# Micro_y_BT.net
KiCad netlist of a schematic drawn in Altium Designer
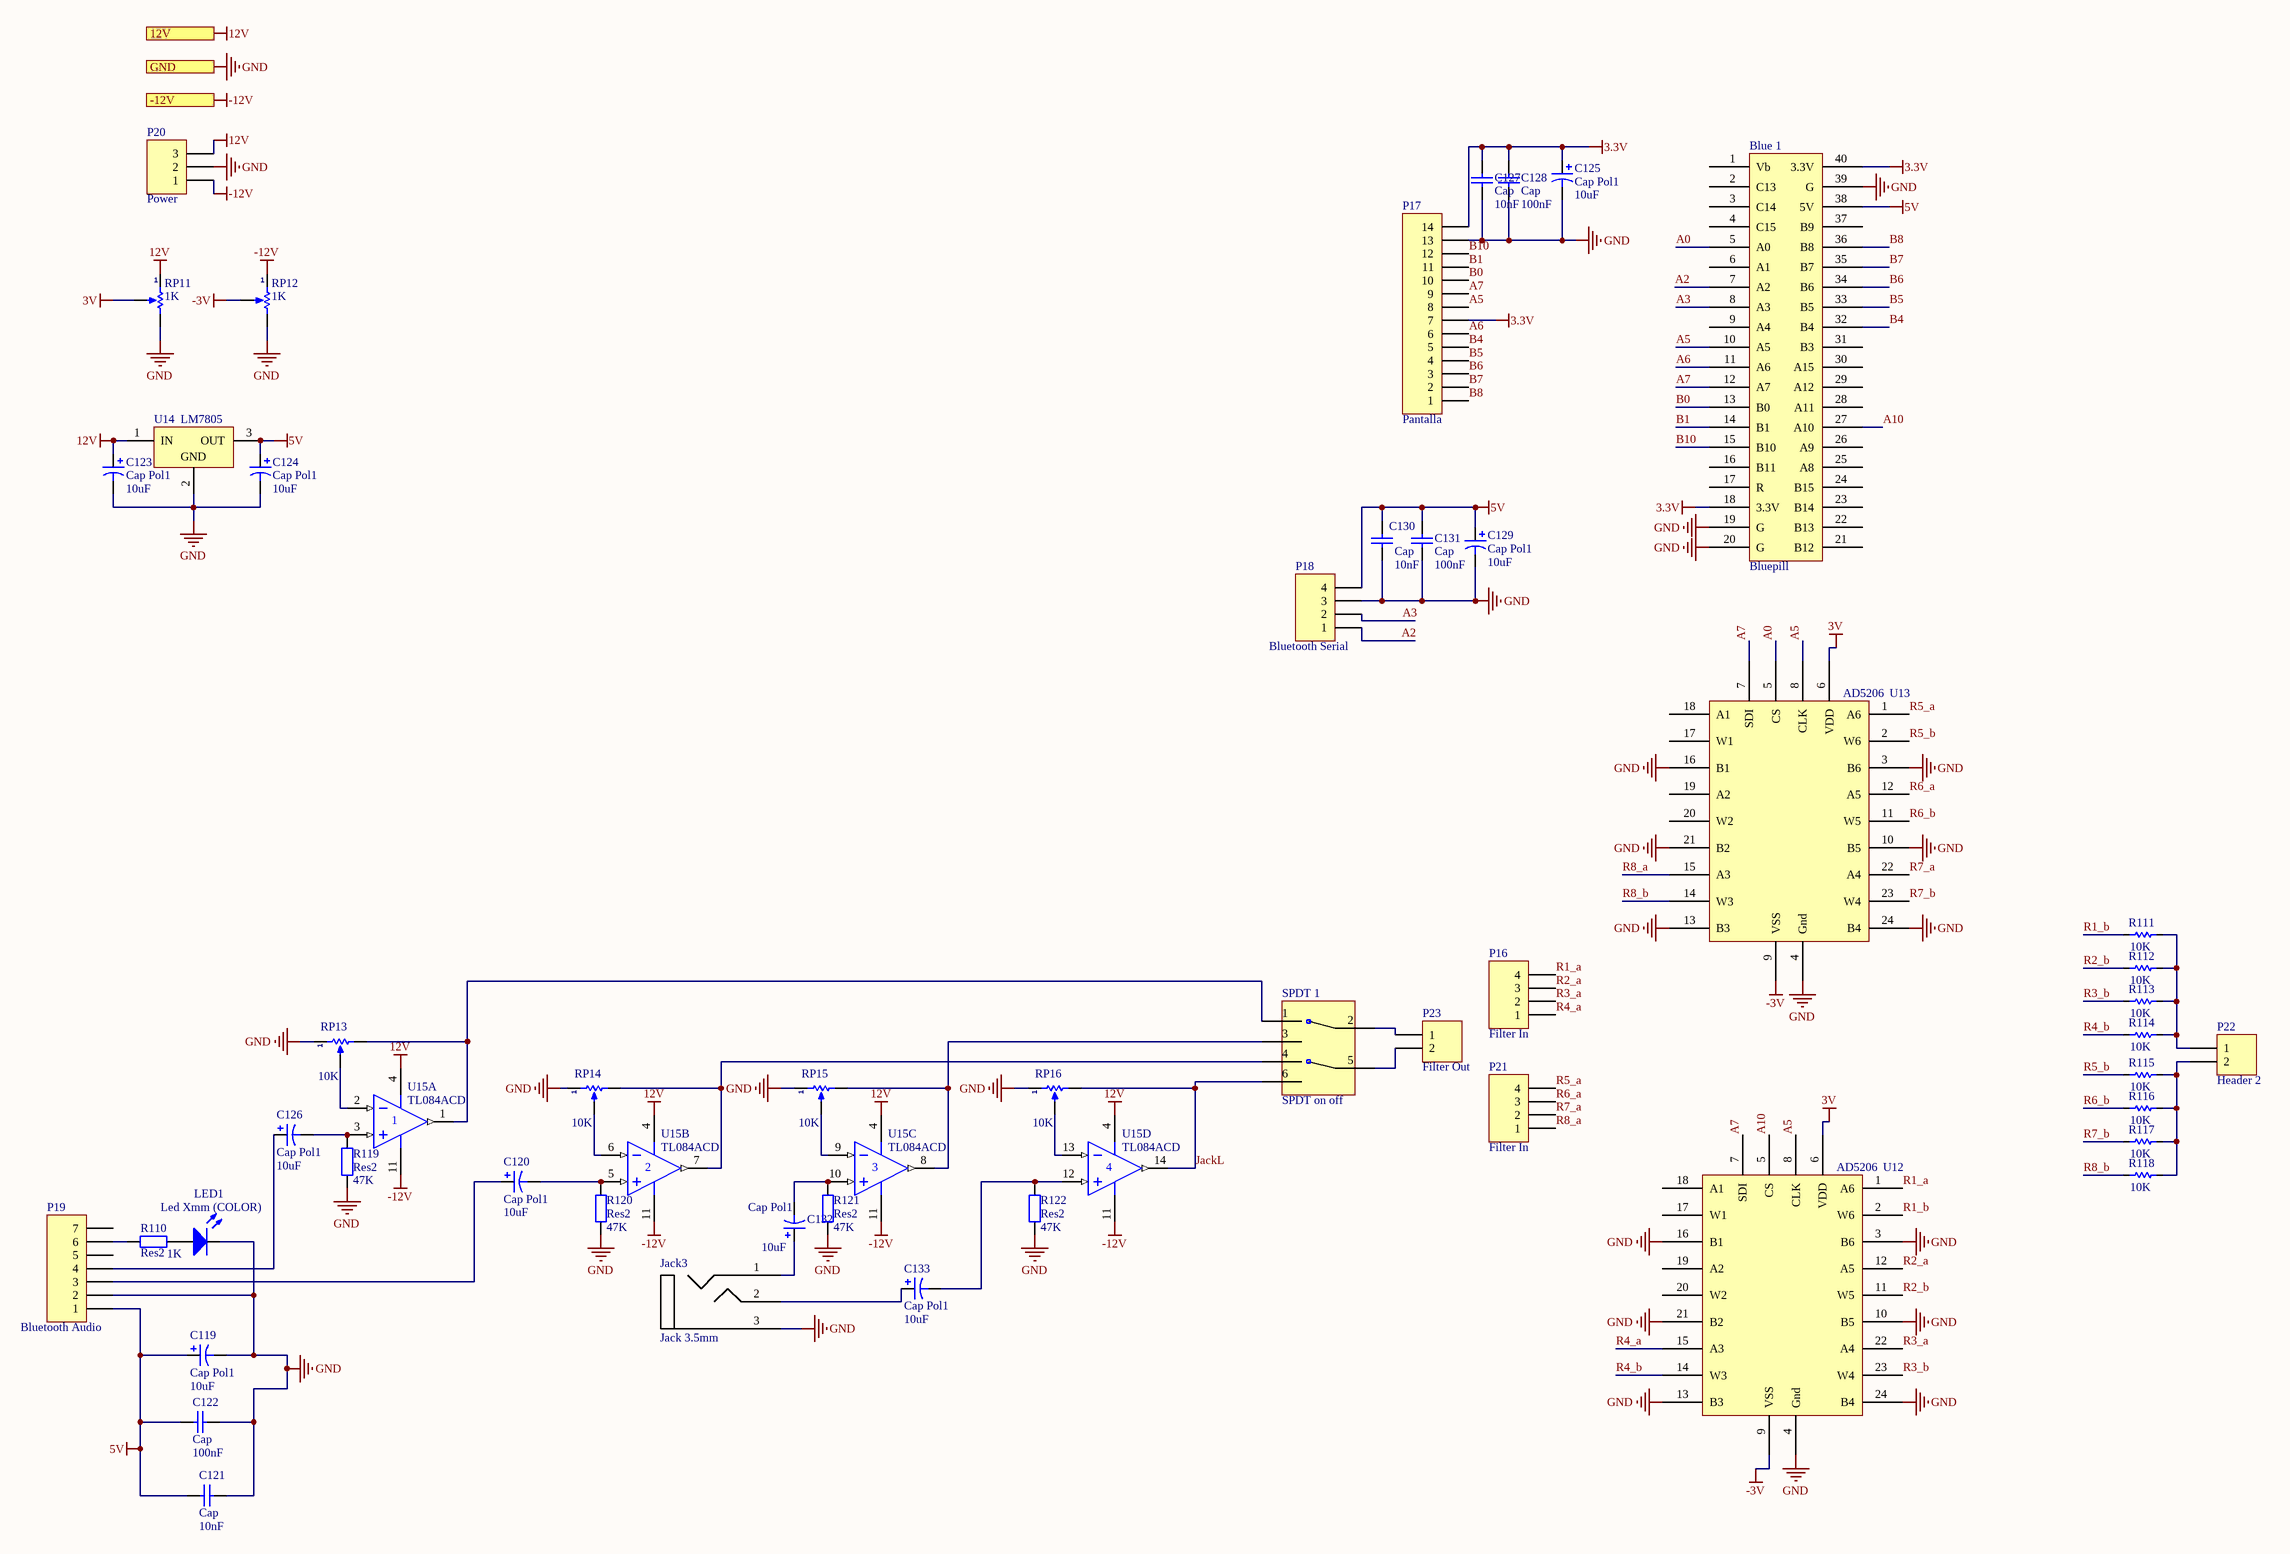
[diagram p0: Micro y BT.SchDoc]

(export (version "E")
  (design (tool "Eeschema 10.0.6"))
  (components
    (comp (ref "Blue 1")
      (value "Bluepill")
      (footprint "Bluepill")
      (libsource (lib "Userlib") (part "Bluepill"))
    )
    (comp (ref "C119")
      (value "Cap Pol1")
      (footprint "CAPR D250 H450 R100 mil")
      (description "Polarized Capacitor (Radial)")
      (fields (field (name "ALTIUM_VALUE") "10uF") (field (name "PUBLISHER") "Altium Limited"))
      (libsource (lib "Miscellaneous Devices") (part "Cap Pol1"))
    )
    (comp (ref "C120")
      (value "Cap Pol1")
      (footprint "CAPR D250 H450 R100 mil")
      (description "Polarized Capacitor (Radial)")
      (fields (field (name "ALTIUM_VALUE") "10uF") (field (name "PUBLISHER") "Altium Limited"))
      (libsource (lib "Miscellaneous Devices") (part "Cap Pol1"))
    )
    (comp (ref "C121")
      (value "Cap")
      (footprint "cap 3")
      (description "Capacitor")
      (fields (field (name "ALTIUM_VALUE") "10nF") (field (name "PUBLISHER") "Altium Limited"))
      (libsource (lib "Miscellaneous Devices") (part "Cap"))
    )
    (comp (ref "C122")
      (value "Cap")
      (footprint "CAP DISCO 200mil")
      (description "Capacitor")
      (fields (field (name "ALTIUM_VALUE") "100nF") (field (name "PUBLISHER") "Altium Limited"))
      (libsource (lib "Miscellaneous Devices") (part "Cap"))
    )
    (comp (ref "C123")
      (value "Cap Pol1")
      (footprint "CAPR D250 H450 R100 mil")
      (description "Polarized Capacitor (Radial)")
      (fields (field (name "ALTIUM_VALUE") "10uF") (field (name "PUBLISHER") "Altium Limited"))
      (libsource (lib "Miscellaneous Devices") (part "Cap Pol1"))
    )
    (comp (ref "C124")
      (value "Cap Pol1")
      (footprint "CAPR D250 H450 R100 mil")
      (description "Polarized Capacitor (Radial)")
      (fields (field (name "ALTIUM_VALUE") "10uF") (field (name "PUBLISHER") "Altium Limited"))
      (libsource (lib "Miscellaneous Devices") (part "Cap Pol1"))
    )
    (comp (ref "C125")
      (value "Cap Pol1")
      (footprint "CAPR D250 H450 R100 mil")
      (description "Polarized Capacitor (Radial)")
      (fields (field (name "ALTIUM_VALUE") "10uF") (field (name "PUBLISHER") "Altium Limited"))
      (libsource (lib "Miscellaneous Devices") (part "Cap Pol1"))
    )
    (comp (ref "C126")
      (value "Cap Pol1")
      (footprint "CAPR D250 H450 R100 mil")
      (description "Polarized Capacitor (Radial)")
      (fields (field (name "ALTIUM_VALUE") "10uF") (field (name "PUBLISHER") "Altium Limited"))
      (libsource (lib "Miscellaneous Devices") (part "Cap Pol1"))
    )
    (comp (ref "C127")
      (value "Cap")
      (footprint "RAD-0.3")
      (description "Capacitor")
      (fields (field (name "ALTIUM_VALUE") "10nF") (field (name "PUBLISHER") "Altium Limited"))
      (libsource (lib "Miscellaneous Devices") (part "Cap"))
    )
    (comp (ref "C128")
      (value "Cap")
      (footprint "CAP DISCO 200mil")
      (description "Capacitor")
      (fields (field (name "ALTIUM_VALUE") "100nF") (field (name "PUBLISHER") "Altium Limited"))
      (libsource (lib "Miscellaneous Devices") (part "Cap"))
    )
    (comp (ref "C129")
      (value "Cap Pol1")
      (footprint "CAPR D250 H450 R100 mil")
      (description "Polarized Capacitor (Radial)")
      (fields (field (name "ALTIUM_VALUE") "10uF") (field (name "PUBLISHER") "Altium Limited"))
      (libsource (lib "Miscellaneous Devices") (part "Cap Pol1"))
    )
    (comp (ref "C130")
      (value "Cap")
      (footprint "cap 3")
      (description "Capacitor")
      (fields (field (name "ALTIUM_VALUE") "10nF") (field (name "PUBLISHER") "Altium Limited"))
      (libsource (lib "Miscellaneous Devices") (part "Cap"))
    )
    (comp (ref "C131")
      (value "Cap")
      (footprint "CAP DISCO 200mil")
      (description "Capacitor")
      (fields (field (name "ALTIUM_VALUE") "100nF") (field (name "PUBLISHER") "Altium Limited"))
      (libsource (lib "Miscellaneous Devices") (part "Cap"))
    )
    (comp (ref "C132")
      (value "Cap Pol1")
      (footprint "CAPR D250 H450 R100 mil")
      (description "Polarized Capacitor (Radial)")
      (fields (field (name "ALTIUM_VALUE") "10uF") (field (name "PUBLISHER") "Altium Limited"))
      (libsource (lib "Miscellaneous Devices") (part "Cap Pol1"))
    )
    (comp (ref "C133")
      (value "Cap Pol1")
      (footprint "CAPR D250 H450 R100 mil")
      (description "Polarized Capacitor (Radial)")
      (fields (field (name "ALTIUM_VALUE") "10uF") (field (name "PUBLISHER") "Altium Limited"))
      (libsource (lib "Miscellaneous Devices") (part "Cap Pol1"))
    )
    (comp (ref "Jack3")
      (value "Jack 3.5mm")
      (footprint "jack 3.5mm")
      (libsource (lib "XR2206") (part "Jack 3.5mm"))
    )
    (comp (ref "LED1")
      (value "Diodo Led")
      (footprint "Led 3mm AMARILLO")
      (description "Led 3mm")
      (fields (field (name "VALOR") "Led Xmm (COLOR)"))
      (libsource (lib "RUF-Dispositivos-Grales") (part "Diodo Led"))
    )
    (comp (ref "P16")
      (value "Filter In")
      (footprint "Bornera 4")
      (description "Header, 4-Pin")
      (fields (field (name "PUBLISHER") "Altium Limited"))
      (libsource (lib "Miscellaneous Connectors") (part "MHDR1X4"))
    )
    (comp (ref "P17")
      (value "Pantalla")
      (footprint "HDR1X14")
      (description "Header, 14-Pin")
      (fields (field (name "PUBLISHER") "Altium Limited"))
      (libsource (lib "Miscellaneous Connectors") (part "Header 14"))
    )
    (comp (ref "P18")
      (value "Bluetooth Serial")
      (footprint "HDR1X4")
      (description "Header, 4-Pin")
      (fields (field (name "PUBLISHER") "Altium Limited"))
      (libsource (lib "Miscellaneous Connectors") (part "MHDR1X4"))
    )
    (comp (ref "P19")
      (value "Bluetooth Audio")
      (footprint "HDR1X7")
      (description "Header, 7-Pin")
      (fields (field (name "PUBLISHER") "Altium Limited"))
      (libsource (lib "Miscellaneous Connectors") (part "Header 7"))
    )
    (comp (ref "P20")
      (value "Power")
      (footprint "HDR1X3")
      (description "Header, 3-Pin")
      (fields (field (name "PUBLISHER") "Altium Limited"))
      (libsource (lib "Miscellaneous Connectors") (part "Header 3"))
    )
    (comp (ref "P21")
      (value "Filter In")
      (footprint "Bornera 4")
      (description "Header, 4-Pin")
      (fields (field (name "PUBLISHER") "Altium Limited"))
      (libsource (lib "Miscellaneous Connectors") (part "MHDR1X4"))
    )
    (comp (ref "P22")
      (value "Header 2")
      (footprint "HDR1X2")
      (description "Header, 2-Pin")
      (fields (field (name "PUBLISHER") "Altium Limited"))
      (libsource (lib "Miscellaneous Connectors") (part "Header 2"))
    )
    (comp (ref "P23")
      (value "Filter Out")
      (footprint "HDR1X2")
      (description "Header, 2-Pin")
      (fields (field (name "PUBLISHER") "Altium Limited"))
      (libsource (lib "Miscellaneous Connectors") (part "Header 2"))
    )
    (comp (ref "R110")
      (value "Res2")
      (footprint "1206 resistor")
      (description "Resistor")
      (fields (field (name "ALTIUM_VALUE") "1K") (field (name "PUBLISHER") "Altium Limited"))
      (libsource (lib "") (part "Res2_1"))
    )
    (comp (ref "R111")
      (value "Res SMD")
      (footprint "1206 resistor")
      (description "Res Smd")
      (fields (field (name "VALOR") "10K"))
      (libsource (lib "RUF-Dispositivos-Grales") (part "Res SMD"))
    )
    (comp (ref "R112")
      (value "Res SMD")
      (footprint "1206 resistor")
      (description "Res Smd")
      (fields (field (name "VALOR") "10K"))
      (libsource (lib "RUF-Dispositivos-Grales") (part "Res SMD"))
    )
    (comp (ref "R113")
      (value "Res SMD")
      (footprint "1206 resistor")
      (description "Res Smd")
      (fields (field (name "VALOR") "10K"))
      (libsource (lib "RUF-Dispositivos-Grales") (part "Res SMD"))
    )
    (comp (ref "R114")
      (value "Res SMD")
      (footprint "1206 resistor")
      (description "Res Smd")
      (fields (field (name "VALOR") "10K"))
      (libsource (lib "RUF-Dispositivos-Grales") (part "Res SMD"))
    )
    (comp (ref "R115")
      (value "Res SMD")
      (footprint "1206 resistor")
      (description "Res Smd")
      (fields (field (name "VALOR") "10K"))
      (libsource (lib "RUF-Dispositivos-Grales") (part "Res SMD"))
    )
    (comp (ref "R116")
      (value "Res SMD")
      (footprint "1206 resistor")
      (description "Res Smd")
      (fields (field (name "VALOR") "10K"))
      (libsource (lib "RUF-Dispositivos-Grales") (part "Res SMD"))
    )
    (comp (ref "R117")
      (value "Res SMD")
      (footprint "1206 resistor")
      (description "Res Smd")
      (fields (field (name "VALOR") "10K"))
      (libsource (lib "RUF-Dispositivos-Grales") (part "Res SMD"))
    )
    (comp (ref "R118")
      (value "Res SMD")
      (footprint "1206 resistor")
      (description "Res Smd")
      (fields (field (name "VALOR") "10K"))
      (libsource (lib "RUF-Dispositivos-Grales") (part "Res SMD"))
    )
    (comp (ref "R119")
      (value "Res2")
      (footprint "1206 resistor")
      (description "Resistor")
      (fields (field (name "ALTIUM_VALUE") "47K") (field (name "PUBLISHER") "Altium Limited"))
      (libsource (lib "Miscellaneous Devices") (part "Res2"))
    )
    (comp (ref "R120")
      (value "Res2")
      (footprint "1206 resistor")
      (description "Resistor")
      (fields (field (name "ALTIUM_VALUE") "47K") (field (name "PUBLISHER") "Altium Limited"))
      (libsource (lib "Miscellaneous Devices") (part "Res2"))
    )
    (comp (ref "R121")
      (value "Res2")
      (footprint "1206 resistor")
      (description "Resistor")
      (fields (field (name "ALTIUM_VALUE") "47K") (field (name "PUBLISHER") "Altium Limited"))
      (libsource (lib "Miscellaneous Devices") (part "Res2"))
    )
    (comp (ref "R122")
      (value "Res2")
      (footprint "1206 resistor")
      (description "Resistor")
      (fields (field (name "ALTIUM_VALUE") "47K") (field (name "PUBLISHER") "Altium Limited"))
      (libsource (lib "Miscellaneous Devices") (part "Res2"))
    )
    (comp (ref "RP11")
      (value "Trimpot")
      (footprint "Trimpot Multivuelta Vertical")
      (description "Preset")
      (fields (field (name "VALOR") "1K"))
      (libsource (lib "RUF-Dispositivos-Grales") (part "Trimpot"))
    )
    (comp (ref "RP12")
      (value "Trimpot")
      (footprint "Trimpot Multivuelta Vertical")
      (description "Preset")
      (fields (field (name "VALOR") "1K"))
      (libsource (lib "RUF-Dispositivos-Grales") (part "Trimpot"))
    )
    (comp (ref "RP13")
      (value "Trimpot")
      (footprint "Trimpot Multivuelta Vertical")
      (description "Preset")
      (fields (field (name "VALOR") "10K"))
      (libsource (lib "RUF-Dispositivos-Grales") (part "Trimpot"))
    )
    (comp (ref "RP14")
      (value "Trimpot")
      (footprint "Trimpot Multivuelta Vertical")
      (description "Preset")
      (fields (field (name "VALOR") "10K"))
      (libsource (lib "RUF-Dispositivos-Grales") (part "Trimpot"))
    )
    (comp (ref "RP15")
      (value "Trimpot")
      (footprint "Trimpot Multivuelta Vertical")
      (description "Preset")
      (fields (field (name "VALOR") "10K"))
      (libsource (lib "RUF-Dispositivos-Grales") (part "Trimpot"))
    )
    (comp (ref "RP16")
      (value "Trimpot")
      (footprint "Trimpot Multivuelta Vertical")
      (description "Preset")
      (fields (field (name "VALOR") "10K"))
      (libsource (lib "RUF-Dispositivos-Grales") (part "Trimpot"))
    )
    (comp (ref "SPDT 1")
      (value "SPDT on off")
      (footprint "DIP-6")
      (libsource (lib "Userlib") (part "SPDT on off"))
    )
    (comp (ref "U12") (value "AD5206") (footprint "948H-01") (libsource (lib "Userlib") (part "AD5206")))
    (comp (ref "U13") (value "AD5206") (footprint "948H-01") (libsource (lib "Userlib") (part "AD5206")))
    (comp (ref "U14")
      (value "LM7805")
      (footprint "TO-220_FullPak")
      (description "3-Terminal Positive Regulators, 3-pin TO-92")
      (fields
        (field (name "PARTNUMBER") "LM78L12ACZ")
        (field (name "MANUFACTURER") "National Semiconductor")
        (field (name "PUBLISHER") "Altium Limited")
      )
      (libsource (lib "NSC LDO") (part "LM78L12ACZ"))
    )
    (comp (ref "U15")
      (value "TL084ACD")
      (footprint "751A-02_N")
      (description "JFET-Input Operational Amplifier")
      (fields (field (name "PUBLISHER") "Altium Limited"))
      (libsource (lib "Motorola Amplifier Operational Amplifier") (part "TL084ACD"))
    )
  )
  (nets
    (net (code "1") (name "-3V") (class "Default")
      (node (ref "RP12") (pin "3") (pinfunction "TAP_3") (pintype "passive"))
      (node (ref "U12") (pin "9") (pinfunction "VSS_9") (pintype "passive"))
      (node (ref "U13") (pin "9") (pinfunction "VSS_9") (pintype "passive"))
    )
    (net (code "2") (name "-12V") (class "Default")
      (node (ref "P20") (pin "1") (pinfunction "1_1") (pintype "passive"))
      (node (ref "RP12") (pin "1") (pinfunction "TOP_1") (pintype "passive"))
      (node (ref "U15") (pin "11") (pinfunction "V-_11") (pintype "power_in"))
    )
    (net (code "3") (name "/A0") (class "Default")
      (node (ref "Blue 1") (pin "5") (pinfunction "A0_5") (pintype "passive"))
      (node (ref "U13") (pin "5") (pinfunction "CS_5") (pintype "passive"))
    )
    (net (code "4") (name "/A2") (class "Default")
      (node (ref "Blue 1") (pin "7") (pinfunction "A2_7") (pintype "passive"))
      (node (ref "P18") (pin "1") (pinfunction "1_1") (pintype "passive"))
    )
    (net (code "5") (name "/A3") (class "Default")
      (node (ref "Blue 1") (pin "8") (pinfunction "A3_8") (pintype "passive"))
      (node (ref "P18") (pin "2") (pinfunction "2_2") (pintype "passive"))
    )
    (net (code "6") (name "/A5") (class "Default")
      (node (ref "Blue 1") (pin "10") (pinfunction "A5_10") (pintype "passive"))
      (node (ref "P17") (pin "8") (pinfunction "8_8") (pintype "passive"))
      (node (ref "U12") (pin "8") (pinfunction "CLK_8") (pintype "passive"))
      (node (ref "U13") (pin "8") (pinfunction "CLK_8") (pintype "passive"))
    )
    (net (code "7") (name "/A6") (class "Default")
      (node (ref "Blue 1") (pin "11") (pinfunction "A6_11") (pintype "passive"))
      (node (ref "P17") (pin "6") (pinfunction "6_6") (pintype "passive"))
    )
    (net (code "8") (name "/A7") (class "Default")
      (node (ref "Blue 1") (pin "12") (pinfunction "A7_12") (pintype "passive"))
      (node (ref "P17") (pin "9") (pinfunction "9_9") (pintype "passive"))
      (node (ref "U12") (pin "7") (pinfunction "SDI_7") (pintype "passive"))
      (node (ref "U13") (pin "7") (pinfunction "SDI_7") (pintype "passive"))
    )
    (net (code "9") (name "/A10") (class "Default")
      (node (ref "Blue 1") (pin "27") (pinfunction "A10_27") (pintype "passive"))
      (node (ref "U12") (pin "5") (pinfunction "CS_5") (pintype "passive"))
    )
    (net (code "10") (name "/B0") (class "Default")
      (node (ref "Blue 1") (pin "13") (pinfunction "B0_13") (pintype "passive"))
      (node (ref "P17") (pin "10") (pinfunction "10_10") (pintype "passive"))
    )
    (net (code "11") (name "/B1") (class "Default")
      (node (ref "Blue 1") (pin "14") (pinfunction "B1_14") (pintype "passive"))
      (node (ref "P17") (pin "11") (pinfunction "11_11") (pintype "passive"))
    )
    (net (code "12") (name "/B4") (class "Default")
      (node (ref "Blue 1") (pin "32") (pinfunction "B4_32") (pintype "passive"))
      (node (ref "P17") (pin "5") (pinfunction "5_5") (pintype "passive"))
    )
    (net (code "13") (name "/B5") (class "Default")
      (node (ref "Blue 1") (pin "33") (pinfunction "B5_33") (pintype "passive"))
      (node (ref "P17") (pin "4") (pinfunction "4_4") (pintype "passive"))
    )
    (net (code "14") (name "/B6") (class "Default")
      (node (ref "Blue 1") (pin "34") (pinfunction "B6_34") (pintype "passive"))
      (node (ref "P17") (pin "3") (pinfunction "3_3") (pintype "passive"))
    )
    (net (code "15") (name "/B7") (class "Default")
      (node (ref "Blue 1") (pin "35") (pinfunction "B7_35") (pintype "passive"))
      (node (ref "P17") (pin "2") (pinfunction "2_2") (pintype "passive"))
    )
    (net (code "16") (name "/B8") (class "Default")
      (node (ref "Blue 1") (pin "36") (pinfunction "B8_36") (pintype "passive"))
      (node (ref "P17") (pin "1") (pinfunction "1_1") (pintype "passive"))
    )
    (net (code "17") (name "/B10") (class "Default")
      (node (ref "Blue 1") (pin "15") (pinfunction "B10_15") (pintype "passive"))
      (node (ref "P17") (pin "12") (pinfunction "12_12") (pintype "passive"))
    )
    (net (code "18") (name "/JackL") (class "Default")
      (node (ref "RP16") (pin "2") (pinfunction "BOT_2") (pintype "passive"))
      (node (ref "SPDT 1") (pin "6") (pinfunction "5_6") (pintype "passive"))
      (node (ref "U15") (pin "14") (pinfunction "OUT_14") (pintype "output"))
    )
    (net (code "19") (name "/R1_a") (class "Default")
      (node (ref "P16") (pin "4") (pinfunction "4_4") (pintype "passive"))
      (node (ref "U12") (pin "1") (pinfunction "A6_1") (pintype "passive"))
    )
    (net (code "20") (name "/R1_b") (class "Default")
      (node (ref "R111") (pin "1") (pinfunction "1_1") (pintype "passive"))
      (node (ref "U12") (pin "2") (pinfunction "W6_2") (pintype "passive"))
    )
    (net (code "21") (name "/R2_a") (class "Default")
      (node (ref "P16") (pin "3") (pinfunction "3_3") (pintype "passive"))
      (node (ref "U12") (pin "12") (pinfunction "A5_12") (pintype "passive"))
    )
    (net (code "22") (name "/R2_b") (class "Default")
      (node (ref "R112") (pin "1") (pinfunction "1_1") (pintype "passive"))
      (node (ref "U12") (pin "11") (pinfunction "W5_11") (pintype "passive"))
    )
    (net (code "23") (name "/R3_a") (class "Default")
      (node (ref "P16") (pin "2") (pinfunction "2_2") (pintype "passive"))
      (node (ref "U12") (pin "22") (pinfunction "A4_22") (pintype "passive"))
    )
    (net (code "24") (name "/R3_b") (class "Default")
      (node (ref "R113") (pin "1") (pinfunction "1_1") (pintype "passive"))
      (node (ref "U12") (pin "23") (pinfunction "W4_23") (pintype "passive"))
    )
    (net (code "25") (name "/R4_a") (class "Default")
      (node (ref "P16") (pin "1") (pinfunction "1_1") (pintype "passive"))
      (node (ref "U12") (pin "15") (pinfunction "A3_15") (pintype "passive"))
    )
    (net (code "26") (name "/R4_b") (class "Default")
      (node (ref "R114") (pin "1") (pinfunction "1_1") (pintype "passive"))
      (node (ref "U12") (pin "14") (pinfunction "W3_14") (pintype "passive"))
    )
    (net (code "27") (name "/R5_a") (class "Default")
      (node (ref "P21") (pin "4") (pinfunction "4_4") (pintype "passive"))
      (node (ref "U13") (pin "1") (pinfunction "A6_1") (pintype "passive"))
    )
    (net (code "28") (name "/R5_b") (class "Default")
      (node (ref "R115") (pin "1") (pinfunction "1_1") (pintype "passive"))
      (node (ref "U13") (pin "2") (pinfunction "W6_2") (pintype "passive"))
    )
    (net (code "29") (name "/R6_a") (class "Default")
      (node (ref "P21") (pin "3") (pinfunction "3_3") (pintype "passive"))
      (node (ref "U13") (pin "12") (pinfunction "A5_12") (pintype "passive"))
    )
    (net (code "30") (name "/R6_b") (class "Default")
      (node (ref "R116") (pin "1") (pinfunction "1_1") (pintype "passive"))
      (node (ref "U13") (pin "11") (pinfunction "W5_11") (pintype "passive"))
    )
    (net (code "31") (name "/R7_a") (class "Default")
      (node (ref "P21") (pin "2") (pinfunction "2_2") (pintype "passive"))
      (node (ref "U13") (pin "22") (pinfunction "A4_22") (pintype "passive"))
    )
    (net (code "32") (name "/R7_b") (class "Default")
      (node (ref "R117") (pin "1") (pinfunction "1_1") (pintype "passive"))
      (node (ref "U13") (pin "23") (pinfunction "W4_23") (pintype "passive"))
    )
    (net (code "33") (name "/R8_a") (class "Default")
      (node (ref "P21") (pin "1") (pinfunction "1_1") (pintype "passive"))
      (node (ref "U13") (pin "15") (pinfunction "A3_15") (pintype "passive"))
    )
    (net (code "34") (name "/R8_b") (class "Default")
      (node (ref "R118") (pin "1") (pinfunction "1_1") (pintype "passive"))
      (node (ref "U13") (pin "14") (pinfunction "W3_14") (pintype "passive"))
    )
    (net (code "35") (name "3.3V") (class "Default")
      (node (ref "Blue 1") (pin "18") (pinfunction "3.3V_18") (pintype "passive"))
      (node (ref "Blue 1") (pin "40") (pinfunction "3.3V_40") (pintype "passive"))
      (node (ref "C125") (pin "1") (pinfunction "1_1") (pintype "passive"))
      (node (ref "C127") (pin "2") (pinfunction "2_2") (pintype "passive"))
      (node (ref "C128") (pin "2") (pinfunction "2_2") (pintype "passive"))
      (node (ref "P17") (pin "14") (pinfunction "14_14") (pintype "passive"))
      (node (ref "P17") (pin "7") (pinfunction "7_7") (pintype "passive"))
    )
    (net (code "36") (name "3V") (class "Default")
      (node (ref "RP11") (pin "3") (pinfunction "TAP_3") (pintype "passive"))
      (node (ref "U12") (pin "6") (pinfunction "VDD_6") (pintype "passive"))
      (node (ref "U13") (pin "6") (pinfunction "VDD_6") (pintype "passive"))
    )
    (net (code "37") (name "5V") (class "Default")
      (node (ref "Blue 1") (pin "38") (pinfunction "5V_38") (pintype "passive"))
      (node (ref "C119") (pin "1") (pinfunction "1_1") (pintype "passive"))
      (node (ref "C121") (pin "2") (pinfunction "2_2") (pintype "passive"))
      (node (ref "C122") (pin "2") (pinfunction "2_2") (pintype "passive"))
      (node (ref "C124") (pin "1") (pinfunction "1_1") (pintype "passive"))
      (node (ref "C129") (pin "1") (pinfunction "1_1") (pintype "passive"))
      (node (ref "C130") (pin "2") (pinfunction "2_2") (pintype "passive"))
      (node (ref "C131") (pin "2") (pinfunction "2_2") (pintype "passive"))
      (node (ref "P18") (pin "4") (pinfunction "4_4") (pintype "passive"))
      (node (ref "P19") (pin "1") (pinfunction "1_1") (pintype "passive"))
      (node (ref "U14") (pin "3") (pinfunction "OUT_3") (pintype "power_in"))
    )
    (net (code "38") (name "12V") (class "Default")
      (node (ref "C123") (pin "1") (pinfunction "1_1") (pintype "passive"))
      (node (ref "P20") (pin "3") (pinfunction "3_3") (pintype "passive"))
      (node (ref "RP11") (pin "1") (pinfunction "TOP_1") (pintype "passive"))
      (node (ref "U14") (pin "1") (pinfunction "IN_1") (pintype "power_in"))
      (node (ref "U15") (pin "4") (pinfunction "V+_4") (pintype "power_in"))
    )
    (net (code "39") (name "GND") (class "Default")
      (node (ref "Blue 1") (pin "19") (pinfunction "G_19") (pintype "passive"))
      (node (ref "Blue 1") (pin "20") (pinfunction "G_20") (pintype "passive"))
      (node (ref "Blue 1") (pin "39") (pinfunction "G_39") (pintype "passive"))
      (node (ref "C119") (pin "2") (pinfunction "2_2") (pintype "passive"))
      (node (ref "C121") (pin "1") (pinfunction "1_1") (pintype "passive"))
      (node (ref "C122") (pin "1") (pinfunction "1_1") (pintype "passive"))
      (node (ref "C123") (pin "2") (pinfunction "2_2") (pintype "passive"))
      (node (ref "C124") (pin "2") (pinfunction "2_2") (pintype "passive"))
      (node (ref "C125") (pin "2") (pinfunction "2_2") (pintype "passive"))
      (node (ref "C127") (pin "1") (pinfunction "1_1") (pintype "passive"))
      (node (ref "C128") (pin "1") (pinfunction "1_1") (pintype "passive"))
      (node (ref "C129") (pin "2") (pinfunction "2_2") (pintype "passive"))
      (node (ref "C130") (pin "1") (pinfunction "1_1") (pintype "passive"))
      (node (ref "C131") (pin "1") (pinfunction "1_1") (pintype "passive"))
      (node (ref "Jack3") (pin "3") (pinfunction "Gnd_3") (pintype "passive"))
      (node (ref "LED1") (pin "2") (pinfunction "K_2") (pintype "passive"))
      (node (ref "P17") (pin "13") (pinfunction "13_13") (pintype "passive"))
      (node (ref "P18") (pin "3") (pinfunction "3_3") (pintype "passive"))
      (node (ref "P19") (pin "2") (pinfunction "2_2") (pintype "passive"))
      (node (ref "P20") (pin "2") (pinfunction "2_2") (pintype "passive"))
      (node (ref "R119") (pin "1") (pinfunction "1_1") (pintype "passive"))
      (node (ref "R120") (pin "1") (pinfunction "1_1") (pintype "passive"))
      (node (ref "R121") (pin "1") (pinfunction "1_1") (pintype "passive"))
      (node (ref "R122") (pin "1") (pinfunction "1_1") (pintype "passive"))
      (node (ref "RP11") (pin "2") (pinfunction "BOT_2") (pintype "passive"))
      (node (ref "RP12") (pin "2") (pinfunction "BOT_2") (pintype "passive"))
      (node (ref "RP13") (pin "1") (pinfunction "TOP_1") (pintype "passive"))
      (node (ref "RP14") (pin "1") (pinfunction "TOP_1") (pintype "passive"))
      (node (ref "RP15") (pin "1") (pinfunction "TOP_1") (pintype "passive"))
      (node (ref "RP16") (pin "1") (pinfunction "TOP_1") (pintype "passive"))
      (node (ref "U12") (pin "10") (pinfunction "B5_10") (pintype "passive"))
      (node (ref "U12") (pin "13") (pinfunction "B3_13") (pintype "passive"))
      (node (ref "U12") (pin "16") (pinfunction "B1_16") (pintype "passive"))
      (node (ref "U12") (pin "21") (pinfunction "B2_21") (pintype "passive"))
      (node (ref "U12") (pin "24") (pinfunction "B4_24") (pintype "passive"))
      (node (ref "U12") (pin "3") (pinfunction "B6_3") (pintype "passive"))
      (node (ref "U12") (pin "4") (pinfunction "Gnd_4") (pintype "passive"))
      (node (ref "U13") (pin "10") (pinfunction "B5_10") (pintype "passive"))
      (node (ref "U13") (pin "13") (pinfunction "B3_13") (pintype "passive"))
      (node (ref "U13") (pin "16") (pinfunction "B1_16") (pintype "passive"))
      (node (ref "U13") (pin "21") (pinfunction "B2_21") (pintype "passive"))
      (node (ref "U13") (pin "24") (pinfunction "B4_24") (pintype "passive"))
      (node (ref "U13") (pin "3") (pinfunction "B6_3") (pintype "passive"))
      (node (ref "U13") (pin "4") (pinfunction "Gnd_4") (pintype "passive"))
      (node (ref "U14") (pin "2") (pinfunction "GND_2") (pintype "power_in"))
    )
    (net (code "40") (name "Net-(C120-Pad1)") (class "Default")
      (node (ref "C120") (pin "1") (pinfunction "1_1") (pintype "passive"))
      (node (ref "P19") (pin "3") (pinfunction "3_3") (pintype "passive"))
    )
    (net (code "41") (name "Net-(C126-Pad1)") (class "Default")
      (node (ref "C126") (pin "1") (pinfunction "1_1") (pintype "passive"))
      (node (ref "P19") (pin "4") (pinfunction "4_4") (pintype "passive"))
    )
    (net (code "42") (name "Net-(Jack3-L)") (class "Default")
      (node (ref "C133") (pin "1") (pinfunction "1_1") (pintype "passive"))
      (node (ref "Jack3") (pin "2") (pinfunction "L_2") (pintype "passive"))
    )
    (net (code "43") (name "Net-(Jack3-R)") (class "Default")
      (node (ref "C132") (pin "1") (pinfunction "1_1") (pintype "passive"))
      (node (ref "Jack3") (pin "1") (pinfunction "R_1") (pintype "passive"))
    )
    (net (code "44") (name "Net-(LED1-A)") (class "Default")
      (node (ref "LED1") (pin "1") (pinfunction "A_1") (pintype "passive"))
      (node (ref "R110") (pin "1") (pinfunction "1_1") (pintype "passive"))
    )
    (net (code "45") (name "Net-(P19-Pad6)") (class "Default")
      (node (ref "P19") (pin "6") (pinfunction "6_6") (pintype "passive"))
      (node (ref "R110") (pin "2") (pinfunction "2_2") (pintype "passive"))
    )
    (net (code "46") (name "Net-(P22-Pad1)") (class "Default")
      (node (ref "P22") (pin "1") (pinfunction "1_1") (pintype "passive"))
      (node (ref "R111") (pin "2") (pinfunction "2_2") (pintype "passive"))
      (node (ref "R112") (pin "2") (pinfunction "2_2") (pintype "passive"))
      (node (ref "R113") (pin "2") (pinfunction "2_2") (pintype "passive"))
      (node (ref "R114") (pin "2") (pinfunction "2_2") (pintype "passive"))
    )
    (net (code "47") (name "Net-(P22-Pad2)") (class "Default")
      (node (ref "P22") (pin "2") (pinfunction "2_2") (pintype "passive"))
      (node (ref "R115") (pin "2") (pinfunction "2_2") (pintype "passive"))
      (node (ref "R116") (pin "2") (pinfunction "2_2") (pintype "passive"))
      (node (ref "R117") (pin "2") (pinfunction "2_2") (pintype "passive"))
      (node (ref "R118") (pin "2") (pinfunction "2_2") (pintype "passive"))
    )
    (net (code "48") (name "Net-(RP13-BOT)") (class "Default")
      (node (ref "RP13") (pin "2") (pinfunction "BOT_2") (pintype "passive"))
      (node (ref "SPDT 1") (pin "1") (pinfunction "B15_1") (pintype "passive"))
      (node (ref "U15") (pin "1") (pinfunction "OUT_1") (pintype "output"))
    )
    (net (code "49") (name "Net-(RP13-TAP)") (class "Default")
      (node (ref "RP13") (pin "3") (pinfunction "TAP_3") (pintype "passive"))
      (node (ref "U15") (pin "2") (pinfunction "IN-_2") (pintype "input"))
    )
    (net (code "50") (name "Net-(RP14-BOT)") (class "Default")
      (node (ref "RP14") (pin "2") (pinfunction "BOT_2") (pintype "passive"))
      (node (ref "SPDT 1") (pin "4") (pinfunction "B18_4") (pintype "passive"))
      (node (ref "U15") (pin "7") (pinfunction "OUT_7") (pintype "output"))
    )
    (net (code "51") (name "Net-(RP14-TAP)") (class "Default")
      (node (ref "RP14") (pin "3") (pinfunction "TAP_3") (pintype "passive"))
      (node (ref "U15") (pin "6") (pinfunction "IN-_6") (pintype "input"))
    )
    (net (code "52") (name "Net-(RP15-BOT)") (class "Default")
      (node (ref "RP15") (pin "2") (pinfunction "BOT_2") (pintype "passive"))
      (node (ref "SPDT 1") (pin "3") (pinfunction "B16_3") (pintype "passive"))
      (node (ref "U15") (pin "8") (pinfunction "OUT_8") (pintype "output"))
    )
    (net (code "53") (name "Net-(RP15-TAP)") (class "Default")
      (node (ref "RP15") (pin "3") (pinfunction "TAP_3") (pintype "passive"))
      (node (ref "U15") (pin "9") (pinfunction "IN-_9") (pintype "input"))
    )
    (net (code "54") (name "Net-(RP16-TAP)") (class "Default")
      (node (ref "RP16") (pin "3") (pinfunction "TAP_3") (pintype "passive"))
      (node (ref "U15") (pin "13") (pinfunction "IN-_13") (pintype "input"))
    )
    (net (code "55") (name "Net-(SPDT 1-6)") (class "Default")
      (node (ref "P23") (pin "2") (pinfunction "2_2") (pintype "passive"))
      (node (ref "SPDT 1") (pin "5") (pinfunction "6_5") (pintype "passive"))
    )
    (net (code "56") (name "Net-(SPDT 1-B17)") (class "Default")
      (node (ref "P23") (pin "1") (pinfunction "1_1") (pintype "passive"))
      (node (ref "SPDT 1") (pin "2") (pinfunction "B17_2") (pintype "passive"))
    )
    (net (code "57") (name "Net-(U15A-IN+)") (class "Default")
      (node (ref "C126") (pin "2") (pinfunction "2_2") (pintype "passive"))
      (node (ref "R119") (pin "2") (pinfunction "2_2") (pintype "passive"))
      (node (ref "U15") (pin "3") (pinfunction "IN+_3") (pintype "input"))
    )
    (net (code "58") (name "Net-(U15B-IN+)") (class "Default")
      (node (ref "C120") (pin "2") (pinfunction "2_2") (pintype "passive"))
      (node (ref "R120") (pin "2") (pinfunction "2_2") (pintype "passive"))
      (node (ref "U15") (pin "5") (pinfunction "IN+_5") (pintype "input"))
    )
    (net (code "59") (name "Net-(U15C-IN+)") (class "Default")
      (node (ref "C132") (pin "2") (pinfunction "2_2") (pintype "passive"))
      (node (ref "R121") (pin "2") (pinfunction "2_2") (pintype "passive"))
      (node (ref "U15") (pin "10") (pinfunction "IN+_10") (pintype "input"))
    )
    (net (code "60") (name "Net-(U15D-IN+)") (class "Default")
      (node (ref "C133") (pin "2") (pinfunction "2_2") (pintype "passive"))
      (node (ref "R122") (pin "2") (pinfunction "2_2") (pintype "passive"))
      (node (ref "U15") (pin "12") (pinfunction "IN+_12") (pintype "input"))
    )
    (net (code "61") (name "unconnected-(Blue 1-A1-Pad6)") (class "Default")
      (node (ref "Blue 1") (pin "6") (pinfunction "A1_6") (pintype "passive"))
    )
    (net (code "62") (name "unconnected-(Blue 1-A4-Pad9)") (class "Default")
      (node (ref "Blue 1") (pin "9") (pinfunction "A4_9") (pintype "passive"))
    )
    (net (code "63") (name "unconnected-(Blue 1-A8-Pad25)") (class "Default")
      (node (ref "Blue 1") (pin "25") (pinfunction "A8_25") (pintype "passive"))
    )
    (net (code "64") (name "unconnected-(Blue 1-A9-Pad26)") (class "Default")
      (node (ref "Blue 1") (pin "26") (pinfunction "A9_26") (pintype "passive"))
    )
    (net (code "65") (name "unconnected-(Blue 1-A11-Pad28)") (class "Default")
      (node (ref "Blue 1") (pin "28") (pinfunction "A11_28") (pintype "passive"))
    )
    (net (code "66") (name "unconnected-(Blue 1-A12-Pad29)") (class "Default")
      (node (ref "Blue 1") (pin "29") (pinfunction "A12_29") (pintype "passive"))
    )
    (net (code "67") (name "unconnected-(Blue 1-A15-Pad30)") (class "Default")
      (node (ref "Blue 1") (pin "30") (pinfunction "A15_30") (pintype "passive"))
    )
    (net (code "68") (name "unconnected-(Blue 1-B3-Pad31)") (class "Default")
      (node (ref "Blue 1") (pin "31") (pinfunction "B3_31") (pintype "passive"))
    )
    (net (code "69") (name "unconnected-(Blue 1-B9-Pad37)") (class "Default")
      (node (ref "Blue 1") (pin "37") (pinfunction "B9_37") (pintype "passive"))
    )
    (net (code "70") (name "unconnected-(Blue 1-B11-Pad16)") (class "Default")
      (node (ref "Blue 1") (pin "16") (pinfunction "B11_16") (pintype "passive"))
    )
    (net (code "71") (name "unconnected-(Blue 1-B12-Pad21)") (class "Default")
      (node (ref "Blue 1") (pin "21") (pinfunction "B12_21") (pintype "passive"))
    )
    (net (code "72") (name "unconnected-(Blue 1-B13-Pad22)") (class "Default")
      (node (ref "Blue 1") (pin "22") (pinfunction "B13_22") (pintype "passive"))
    )
    (net (code "73") (name "unconnected-(Blue 1-B14-Pad23)") (class "Default")
      (node (ref "Blue 1") (pin "23") (pinfunction "B14_23") (pintype "passive"))
    )
    (net (code "74") (name "unconnected-(Blue 1-B15-Pad24)") (class "Default")
      (node (ref "Blue 1") (pin "24") (pinfunction "B15_24") (pintype "passive"))
    )
    (net (code "75") (name "unconnected-(Blue 1-C13-Pad2)") (class "Default")
      (node (ref "Blue 1") (pin "2") (pinfunction "C13_2") (pintype "passive"))
    )
    (net (code "76") (name "unconnected-(Blue 1-C14-Pad3)") (class "Default")
      (node (ref "Blue 1") (pin "3") (pinfunction "C14_3") (pintype "passive"))
    )
    (net (code "77") (name "unconnected-(Blue 1-C15-Pad4)") (class "Default")
      (node (ref "Blue 1") (pin "4") (pinfunction "C15_4") (pintype "passive"))
    )
    (net (code "78") (name "unconnected-(Blue 1-R-Pad17)") (class "Default")
      (node (ref "Blue 1") (pin "17") (pinfunction "R_17") (pintype "passive"))
    )
    (net (code "79") (name "unconnected-(Blue 1-Vb-Pad1)") (class "Default")
      (node (ref "Blue 1") (pin "1") (pinfunction "Vb_1") (pintype "passive"))
    )
    (net (code "80") (name "unconnected-(P19-Pad5)") (class "Default")
      (node (ref "P19") (pin "5") (pinfunction "5_5") (pintype "passive"))
    )
    (net (code "81") (name "unconnected-(P19-Pad7)") (class "Default")
      (node (ref "P19") (pin "7") (pinfunction "7_7") (pintype "passive"))
    )
    (net (code "82") (name "unconnected-(U12-A1-Pad18)") (class "Default")
      (node (ref "U12") (pin "18") (pinfunction "A1_18") (pintype "passive"))
    )
    (net (code "83") (name "unconnected-(U12-A2-Pad19)") (class "Default")
      (node (ref "U12") (pin "19") (pinfunction "A2_19") (pintype "passive"))
    )
    (net (code "84") (name "unconnected-(U12-W1-Pad17)") (class "Default")
      (node (ref "U12") (pin "17") (pinfunction "W1_17") (pintype "passive"))
    )
    (net (code "85") (name "unconnected-(U12-W2-Pad20)") (class "Default")
      (node (ref "U12") (pin "20") (pinfunction "W2_20") (pintype "passive"))
    )
    (net (code "86") (name "unconnected-(U13-A1-Pad18)") (class "Default")
      (node (ref "U13") (pin "18") (pinfunction "A1_18") (pintype "passive"))
    )
    (net (code "87") (name "unconnected-(U13-A2-Pad19)") (class "Default")
      (node (ref "U13") (pin "19") (pinfunction "A2_19") (pintype "passive"))
    )
    (net (code "88") (name "unconnected-(U13-W1-Pad17)") (class "Default")
      (node (ref "U13") (pin "17") (pinfunction "W1_17") (pintype "passive"))
    )
    (net (code "89") (name "unconnected-(U13-W2-Pad20)") (class "Default")
      (node (ref "U13") (pin "20") (pinfunction "W2_20") (pintype "passive"))
    )
  )
)
